# RJ45_Breakout.net
KiCad netlist of a schematic drawn in EAGLE
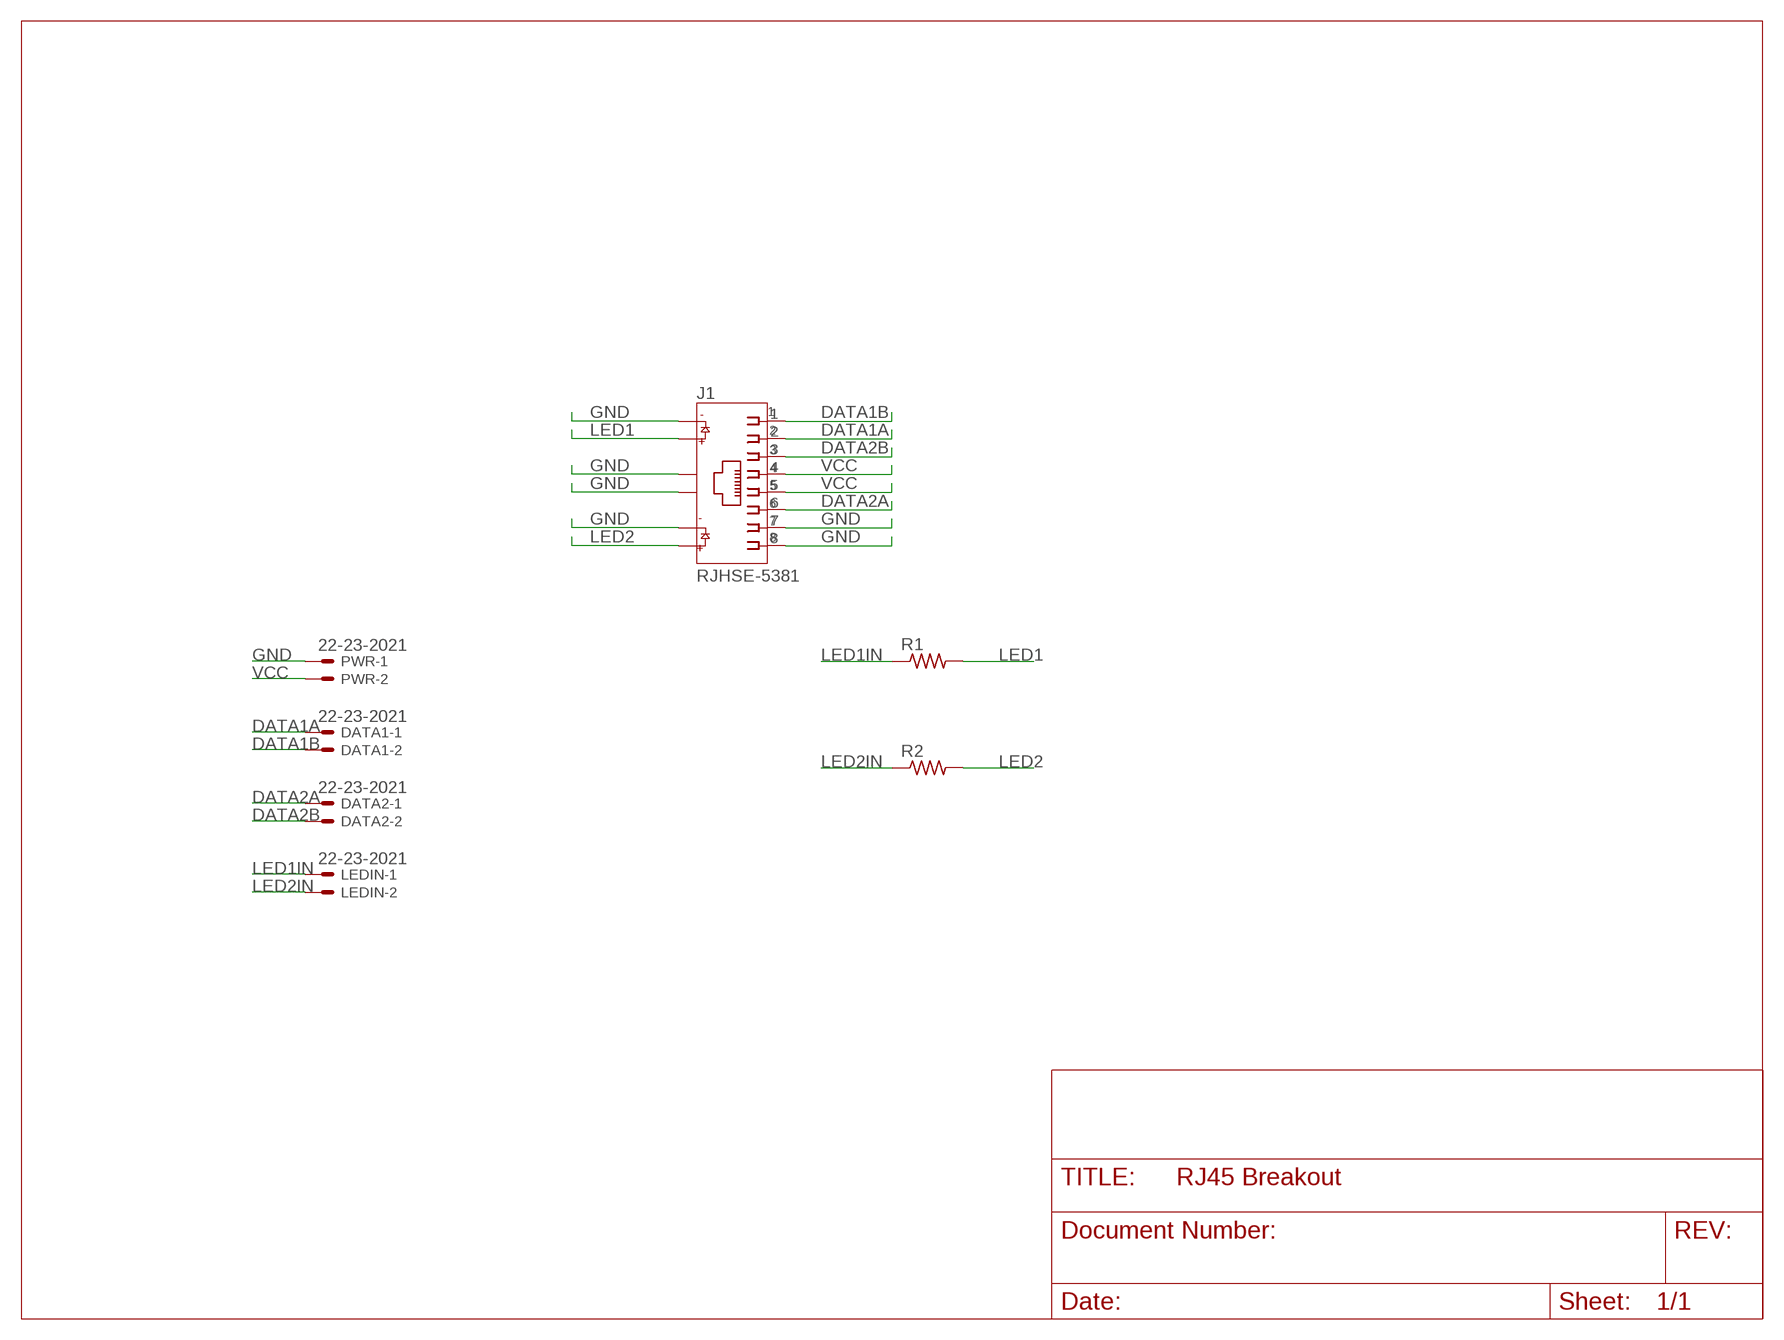
[diagram p0: schematic, sheet 1]

(export (version "E")
  (design (tool "Eeschema 10.0.6"))
  (components
    (comp (ref "DATA1")
      (value "22-23-2021")
      (footprint "eagle-import:22-23-2021")
      (fields (field (name "MF") "MOLEX"))
      (libsource (lib "eagle-import") (part "22-23-2021"))
    )
    (comp (ref "DATA2")
      (value "22-23-2021")
      (footprint "eagle-import:22-23-2021")
      (fields (field (name "MF") "MOLEX"))
      (libsource (lib "eagle-import") (part "22-23-2021"))
    )
    (comp (ref "J1")
      (value "RJHSE-5381")
      (footprint "eagle-import:AMPHENOL_RJHSE-5381")
      (fields (field (name "MF") "Amphenol ICC"))
      (libsource (lib "eagle-import") (part "RJHSE-5381"))
    )
    (comp (ref "LEDIN")
      (value "22-23-2021")
      (footprint "eagle-import:22-23-2021")
      (fields (field (name "MF") "MOLEX"))
      (libsource (lib "eagle-import") (part "22-23-2021"))
    )
    (comp (ref "PWR")
      (value "22-23-2021")
      (footprint "eagle-import:22-23-2021")
      (fields (field (name "MF") "MOLEX"))
      (libsource (lib "eagle-import") (part "22-23-2021"))
    )
    (comp (ref "R1")
      (value "R-US_0207/10")
      (footprint "eagle-import:0207_10")
      (libsource (lib "eagle-import") (part "R-US_0207/10"))
    )
    (comp (ref "R2")
      (value "R-US_0207/10")
      (footprint "eagle-import:0207_10")
      (libsource (lib "eagle-import") (part "R-US_0207/10"))
    )
  )
  (nets
    (net (code "1") (name "/DATA1A") (class "Default")
      (node (ref "DATA1") (pin "1") (pinfunction "S_1") (pintype "passive"))
      (node (ref "J1") (pin "2") (pinfunction "2_2") (pintype "passive"))
    )
    (net (code "2") (name "/DATA1B") (class "Default")
      (node (ref "DATA1") (pin "2") (pinfunction "S_2") (pintype "passive"))
      (node (ref "J1") (pin "1") (pinfunction "1_1") (pintype "passive"))
    )
    (net (code "3") (name "/DATA2A") (class "Default")
      (node (ref "DATA2") (pin "1") (pinfunction "S_1") (pintype "passive"))
      (node (ref "J1") (pin "6") (pinfunction "6_6") (pintype "passive"))
    )
    (net (code "4") (name "/DATA2B") (class "Default")
      (node (ref "DATA2") (pin "2") (pinfunction "S_2") (pintype "passive"))
      (node (ref "J1") (pin "3") (pinfunction "3_3") (pintype "passive"))
    )
    (net (code "5") (name "/GND") (class "Default")
      (node (ref "J1") (pin "11") (pinfunction "11_11") (pintype "passive"))
      (node (ref "J1") (pin "7") (pinfunction "7_7") (pintype "passive"))
      (node (ref "J1") (pin "8") (pinfunction "8_8") (pintype "passive"))
      (node (ref "J1") (pin "9") (pinfunction "9_9") (pintype "passive"))
      (node (ref "J1") (pin "S1") (pinfunction "S1_S1") (pintype "passive"))
      (node (ref "J1") (pin "S2") (pinfunction "S2_S2") (pintype "passive"))
      (node (ref "PWR") (pin "1") (pinfunction "S_1") (pintype "passive"))
    )
    (net (code "6") (name "/LED1") (class "Default")
      (node (ref "J1") (pin "10") (pinfunction "10_10") (pintype "passive"))
      (node (ref "R1") (pin "2") (pinfunction "2_2") (pintype "passive"))
    )
    (net (code "7") (name "/LED1IN") (class "Default")
      (node (ref "LEDIN") (pin "1") (pinfunction "S_1") (pintype "passive"))
      (node (ref "R1") (pin "1") (pinfunction "1_1") (pintype "passive"))
    )
    (net (code "8") (name "/LED2") (class "Default")
      (node (ref "J1") (pin "12") (pinfunction "12_12") (pintype "passive"))
      (node (ref "R2") (pin "2") (pinfunction "2_2") (pintype "passive"))
    )
    (net (code "9") (name "/LED2IN") (class "Default")
      (node (ref "LEDIN") (pin "2") (pinfunction "S_2") (pintype "passive"))
      (node (ref "R2") (pin "1") (pinfunction "1_1") (pintype "passive"))
    )
    (net (code "10") (name "/VCC") (class "Default")
      (node (ref "J1") (pin "4") (pinfunction "4_4") (pintype "passive"))
      (node (ref "J1") (pin "5") (pinfunction "5_5") (pintype "passive"))
      (node (ref "PWR") (pin "2") (pinfunction "S_2") (pintype "passive"))
    )
  )
)
